# Avionica.net
KiCad netlist of a schematic drawn in EAGLE
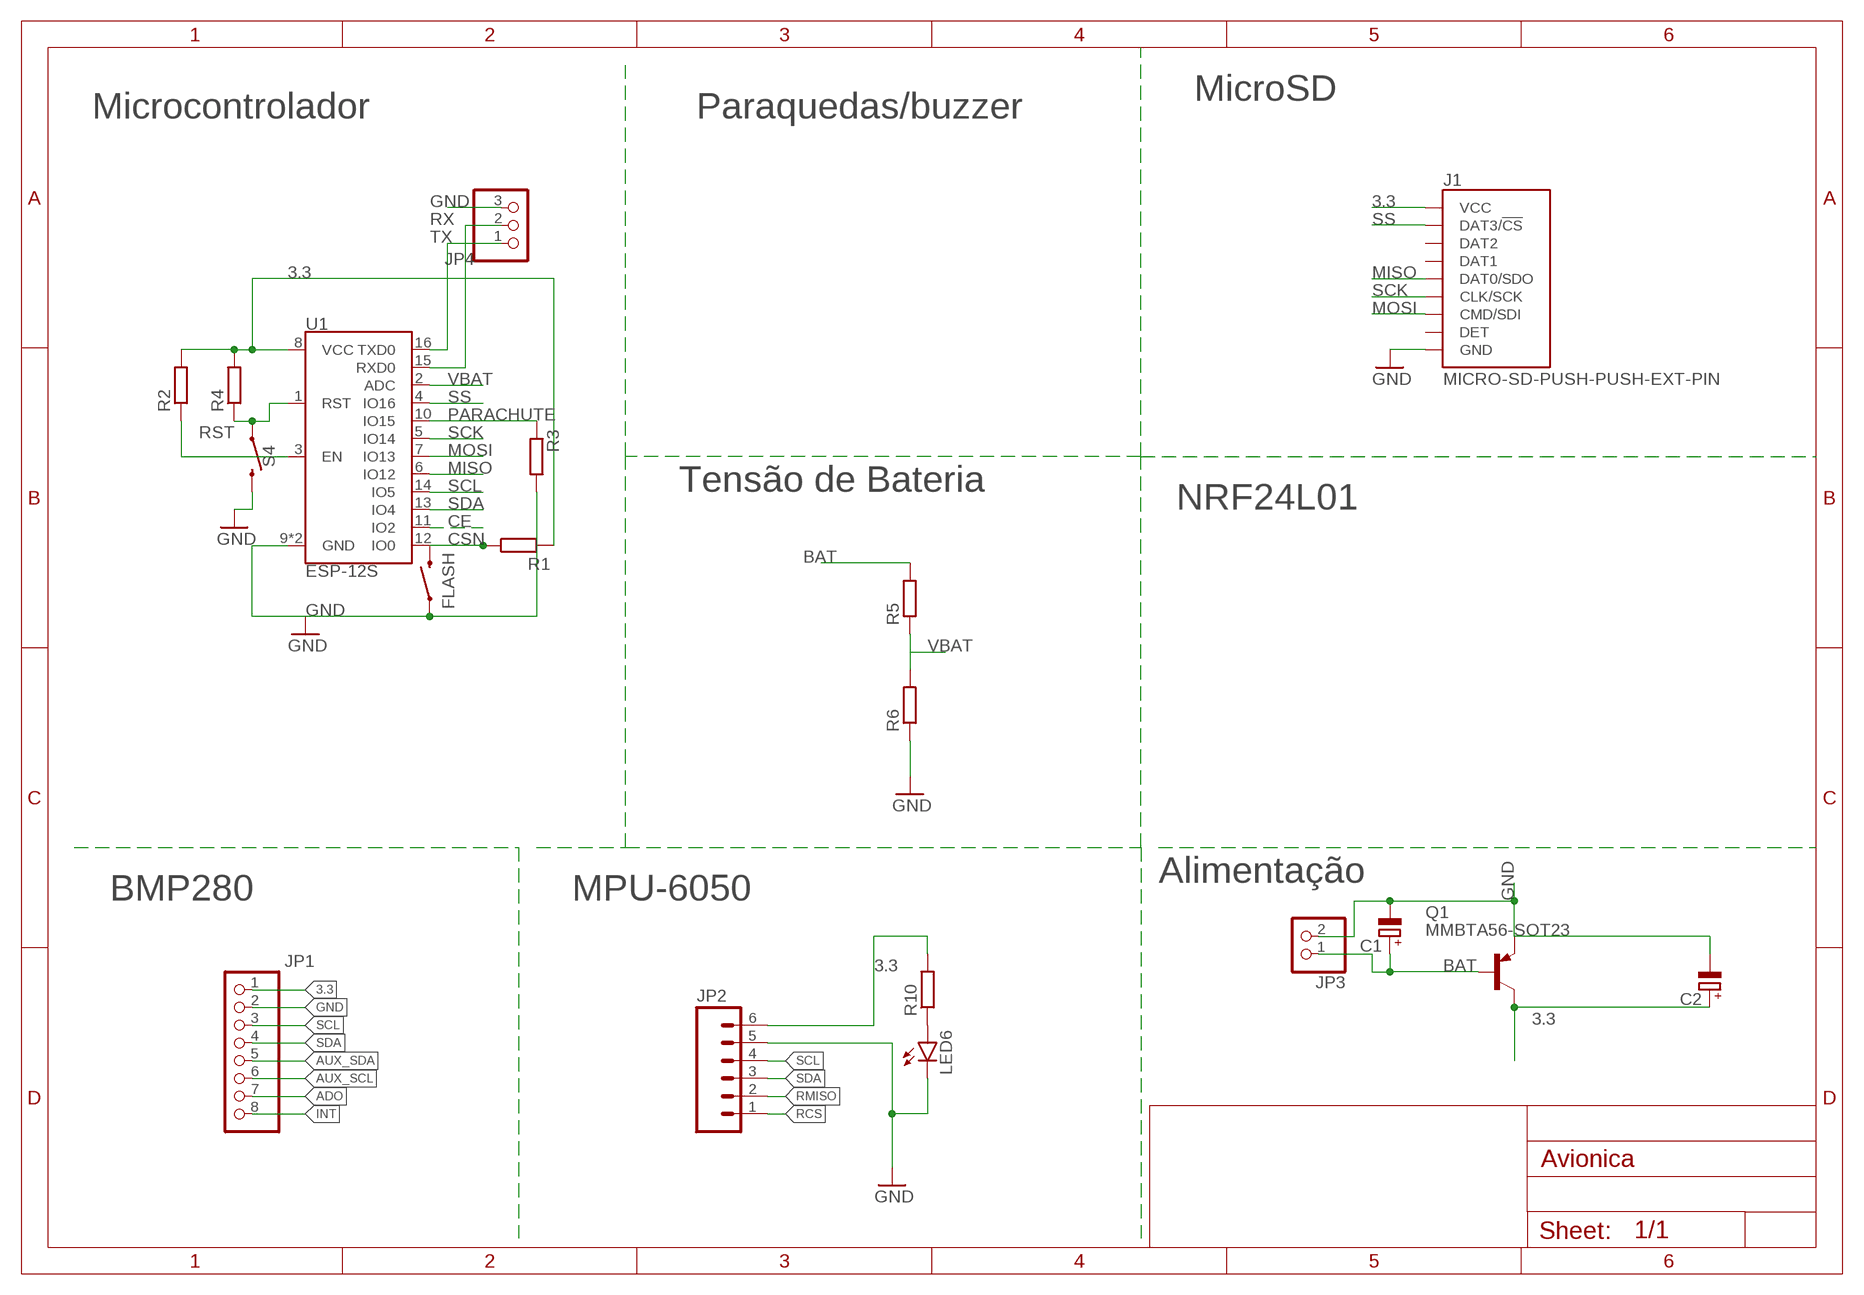
[diagram p0: schematic, sheet 1]

(export (version "E")
  (design (tool "Eeschema 10.0.6"))
  (components
    (comp (ref "C1")
      (value "CPOL-EUE1.8-4")
      (footprint "eagle-import:E1,8-4")
      (libsource (lib "eagle-import") (part "CPOL-EUE1.8-4"))
    )
    (comp (ref "C2")
      (value "CPOL-EUE1.8-4")
      (footprint "eagle-import:E1,8-4")
      (libsource (lib "eagle-import") (part "CPOL-EUE1.8-4"))
    )
    (comp (ref "FLASH")
      (value "MOMENTARY-SWITCH-SPST-SMD-5.2MM-TALL")
      (footprint "eagle-import:TACTILE_SWITCH_SMD_5.2MM")
      (libsource (lib "eagle-import") (part "MOMENTARY-SWITCH-SPST-SMD-5.2MM-TALL"))
    )
    (comp (ref "J1")
      (value "MICRO-SD-PUSH-PUSH-EXT-PIN")
      (footprint "eagle-import:MICROSD-EXTERNALPIN")
      (libsource (lib "eagle-import") (part "MICRO-SD-PUSH-PUSH-EXT-PIN"))
    )
    (comp (ref "JP1")
      (value "PINHD-1X8")
      (footprint "eagle-import:1X08")
      (libsource (lib "eagle-import") (part "PINHD-1X8"))
    )
    (comp (ref "JP2")
      (value "M06NO_SILK_FEMALE_PTH")
      (footprint "eagle-import:1X06_NO_SILK")
      (libsource (lib "eagle-import") (part "M06NO_SILK_FEMALE_PTH"))
    )
    (comp (ref "JP3")
      (value "PINHD-1X2")
      (footprint "eagle-import:1X02")
      (libsource (lib "eagle-import") (part "PINHD-1X2"))
    )
    (comp (ref "JP4")
      (value "PINHD-1X3")
      (footprint "eagle-import:1X03")
      (libsource (lib "eagle-import") (part "PINHD-1X3"))
    )
    (comp (ref "LED6")
      (value "LEDCHIP-LED0805")
      (footprint "eagle-import:CHIP-LED0805")
      (libsource (lib "eagle-import") (part "LEDCHIP-LED0805"))
    )
    (comp (ref "Q1")
      (value "MMBTA56-SOT23")
      (footprint "eagle-import:SOT23")
      (libsource (lib "eagle-import") (part "-?SOT23MMBTA56"))
    )
    (comp (ref "R1")
      (value "R-EU_R0805W")
      (footprint "eagle-import:R0805W")
      (libsource (lib "eagle-import") (part "R-EU_R0805W"))
    )
    (comp (ref "R2")
      (value "R-EU_R0805W")
      (footprint "eagle-import:R0805W")
      (libsource (lib "eagle-import") (part "R-EU_R0805W"))
    )
    (comp (ref "R3")
      (value "R-EU_R0805W")
      (footprint "eagle-import:R0805W")
      (libsource (lib "eagle-import") (part "R-EU_R0805W"))
    )
    (comp (ref "R4")
      (value "R-EU_R0805W")
      (footprint "eagle-import:R0805W")
      (libsource (lib "eagle-import") (part "R-EU_R0805W"))
    )
    (comp (ref "R5")
      (value "R-EU_M0805")
      (footprint "eagle-import:M0805")
      (libsource (lib "eagle-import") (part "R-EU_M0805"))
    )
    (comp (ref "R6")
      (value "R-EU_M0805")
      (footprint "eagle-import:M0805")
      (libsource (lib "eagle-import") (part "R-EU_M0805"))
    )
    (comp (ref "R10")
      (value "R-EU_M0805")
      (footprint "eagle-import:M0805")
      (libsource (lib "eagle-import") (part "R-EU_M0805"))
    )
    (comp (ref "S4")
      (value "MOMENTARY-SWITCH-SPST-SMD-5.2MM-TALL")
      (footprint "eagle-import:TACTILE_SWITCH_SMD_5.2MM")
      (libsource (lib "eagle-import") (part "MOMENTARY-SWITCH-SPST-SMD-5.2MM-TALL"))
    )
    (comp (ref "U1")
      (value "ESP-12S")
      (footprint "eagle-import:ESP-12S")
      (libsource (lib "eagle-import") (part "ESP-12S"))
    )
  )
  (nets
    (net (code "1") (name "/BAT") (class "Default")
      (node (ref "C1") (pin "+") (pinfunction "+_+") (pintype "passive"))
      (node (ref "JP3") (pin "1") (pinfunction "1_1") (pintype "passive"))
      (node (ref "Q1") (pin "1") (pinfunction "B_1") (pintype "passive"))
      (node (ref "R5") (pin "2") (pinfunction "2_2") (pintype "passive"))
    )
    (net (code "2") (name "/CE") (class "Default")
      (node (ref "U1") (pin "11") (pinfunction "IO2_11") (pintype "bidirectional"))
    )
    (net (code "3") (name "/CSN") (class "Default")
      (node (ref "FLASH") (pin "3") (pinfunction "2_3") (pintype "passive"))
      (node (ref "R1") (pin "1") (pinfunction "1_1") (pintype "passive"))
      (node (ref "U1") (pin "12") (pinfunction "IO0_12") (pintype "bidirectional"))
    )
    (net (code "4") (name "/MISO") (class "Default")
      (node (ref "J1") (pin "7") (pinfunction "DAT0/SDO_7") (pintype "bidirectional"))
      (node (ref "U1") (pin "6") (pinfunction "IO12_6") (pintype "bidirectional"))
    )
    (net (code "5") (name "/MOSI") (class "Default")
      (node (ref "J1") (pin "3") (pinfunction "CMD/SDI_3") (pintype "bidirectional"))
      (node (ref "U1") (pin "7") (pinfunction "IO13_7") (pintype "bidirectional"))
    )
    (net (code "6") (name "/PARACHUTE") (class "Default")
      (node (ref "R3") (pin "1") (pinfunction "1_1") (pintype "passive"))
      (node (ref "U1") (pin "10") (pinfunction "IO15_10") (pintype "bidirectional"))
    )
    (net (code "7") (name "/RST") (class "Default")
      (node (ref "R4") (pin "1") (pinfunction "1_1") (pintype "passive"))
      (node (ref "S4") (pin "1") (pinfunction "1_1") (pintype "passive"))
      (node (ref "U1") (pin "1") (pinfunction "RST_1") (pintype "bidirectional"))
    )
    (net (code "8") (name "/RX") (class "Default")
      (node (ref "JP4") (pin "2") (pinfunction "2_2") (pintype "passive"))
      (node (ref "U1") (pin "15") (pinfunction "RXD0_15") (pintype "bidirectional"))
    )
    (net (code "9") (name "/SCK") (class "Default")
      (node (ref "J1") (pin "5") (pinfunction "CLK/SCK_5") (pintype "bidirectional"))
      (node (ref "U1") (pin "5") (pinfunction "IO14_5") (pintype "bidirectional"))
    )
    (net (code "10") (name "/SS") (class "Default")
      (node (ref "J1") (pin "2") (pinfunction "DAT3/~{CS}_2") (pintype "bidirectional"))
      (node (ref "U1") (pin "4") (pinfunction "IO16_4") (pintype "bidirectional"))
    )
    (net (code "11") (name "/TX") (class "Default")
      (node (ref "JP4") (pin "1") (pinfunction "1_1") (pintype "passive"))
      (node (ref "U1") (pin "16") (pinfunction "TXD0_16") (pintype "bidirectional"))
    )
    (net (code "12") (name "/VBAT") (class "Default")
      (node (ref "R5") (pin "1") (pinfunction "1_1") (pintype "passive"))
      (node (ref "R6") (pin "2") (pinfunction "2_2") (pintype "passive"))
      (node (ref "U1") (pin "2") (pinfunction "ADC_2") (pintype "bidirectional"))
    )
    (net (code "13") (name "3.3") (class "Default")
      (node (ref "C2") (pin "+") (pinfunction "+_+") (pintype "passive"))
      (node (ref "J1") (pin "4") (pinfunction "VCC_4") (pintype "bidirectional"))
      (node (ref "JP1") (pin "1") (pinfunction "1_1") (pintype "passive"))
      (node (ref "JP2") (pin "6") (pinfunction "6_6") (pintype "passive"))
      (node (ref "Q1") (pin "3") (pinfunction "C_3") (pintype "passive"))
      (node (ref "R1") (pin "2") (pinfunction "2_2") (pintype "passive"))
      (node (ref "R10") (pin "2") (pinfunction "2_2") (pintype "passive"))
      (node (ref "R2") (pin "2") (pinfunction "2_2") (pintype "passive"))
      (node (ref "R4") (pin "2") (pinfunction "2_2") (pintype "passive"))
      (node (ref "U1") (pin "8") (pinfunction "VCC_8") (pintype "bidirectional"))
    )
    (net (code "14") (name "ADO") (class "Default")
      (node (ref "JP1") (pin "7") (pinfunction "7_7") (pintype "passive"))
    )
    (net (code "15") (name "AUX_SCL") (class "Default")
      (node (ref "JP1") (pin "6") (pinfunction "6_6") (pintype "passive"))
    )
    (net (code "16") (name "AUX_SDA") (class "Default")
      (node (ref "JP1") (pin "5") (pinfunction "5_5") (pintype "passive"))
    )
    (net (code "17") (name "GND") (class "Default")
      (node (ref "C1") (pin "-") (pinfunction "-_-") (pintype "passive"))
      (node (ref "C2") (pin "-") (pinfunction "-_-") (pintype "passive"))
      (node (ref "FLASH") (pin "1") (pinfunction "1_1") (pintype "passive"))
      (node (ref "J1") (pin "10") (pinfunction "GND_10") (pintype "bidirectional"))
      (node (ref "J1") (pin "11") (pinfunction "GND_11") (pintype "bidirectional"))
      (node (ref "J1") (pin "12") (pinfunction "GND_12") (pintype "bidirectional"))
      (node (ref "J1") (pin "13") (pinfunction "GND_13") (pintype "bidirectional"))
      (node (ref "J1") (pin "6") (pinfunction "GND_6") (pintype "bidirectional"))
      (node (ref "JP1") (pin "2") (pinfunction "2_2") (pintype "passive"))
      (node (ref "JP2") (pin "5") (pinfunction "5_5") (pintype "passive"))
      (node (ref "JP3") (pin "2") (pinfunction "2_2") (pintype "passive"))
      (node (ref "JP4") (pin "3") (pinfunction "3_3") (pintype "passive"))
      (node (ref "LED6") (pin "C") (pinfunction "C_C") (pintype "passive"))
      (node (ref "Q1") (pin "2") (pinfunction "E_2") (pintype "passive"))
      (node (ref "R3") (pin "2") (pinfunction "2_2") (pintype "passive"))
      (node (ref "R6") (pin "1") (pinfunction "1_1") (pintype "passive"))
      (node (ref "S4") (pin "3") (pinfunction "2_3") (pintype "passive"))
      (node (ref "U1") (pin "9") (pinfunction "GND_9") (pintype "bidirectional"))
      (node (ref "U1") (pin "P$1") (pinfunction "GND_P$1") (pintype "bidirectional"))
    )
    (net (code "18") (name "INT") (class "Default")
      (node (ref "JP1") (pin "8") (pinfunction "8_8") (pintype "passive"))
    )
    (net (code "19") (name "Net-(LED6-PadA)") (class "Default")
      (node (ref "LED6") (pin "A") (pinfunction "A_A") (pintype "passive"))
      (node (ref "R10") (pin "1") (pinfunction "1_1") (pintype "passive"))
    )
    (net (code "20") (name "Net-(U1-EN)") (class "Default")
      (node (ref "R2") (pin "1") (pinfunction "1_1") (pintype "passive"))
      (node (ref "U1") (pin "3") (pinfunction "EN_3") (pintype "bidirectional"))
    )
    (net (code "21") (name "RCS") (class "Default")
      (node (ref "JP2") (pin "1") (pinfunction "1_1") (pintype "passive"))
    )
    (net (code "22") (name "RMISO") (class "Default")
      (node (ref "JP2") (pin "2") (pinfunction "2_2") (pintype "passive"))
    )
    (net (code "23") (name "SCL") (class "Default")
      (node (ref "JP1") (pin "3") (pinfunction "3_3") (pintype "passive"))
      (node (ref "JP2") (pin "4") (pinfunction "4_4") (pintype "passive"))
      (node (ref "U1") (pin "14") (pinfunction "IO5_14") (pintype "bidirectional"))
    )
    (net (code "24") (name "SDA") (class "Default")
      (node (ref "JP1") (pin "4") (pinfunction "4_4") (pintype "passive"))
      (node (ref "JP2") (pin "3") (pinfunction "3_3") (pintype "passive"))
      (node (ref "U1") (pin "13") (pinfunction "IO4_13") (pintype "bidirectional"))
    )
    (net (code "25") (name "unconnected-(J1-DAT1-Pad8)") (class "Default")
      (node (ref "J1") (pin "8") (pinfunction "DAT1_8") (pintype "bidirectional"))
    )
    (net (code "26") (name "unconnected-(J1-DAT2-Pad1)") (class "Default")
      (node (ref "J1") (pin "1") (pinfunction "DAT2_1") (pintype "bidirectional"))
    )
    (net (code "27") (name "unconnected-(J1-DET-Pad9)") (class "Default")
      (node (ref "J1") (pin "9") (pinfunction "DET_9") (pintype "bidirectional"))
    )
  )
)
